# BoostConverter.net
KiCad netlist of a schematic drawn in Altium Designer
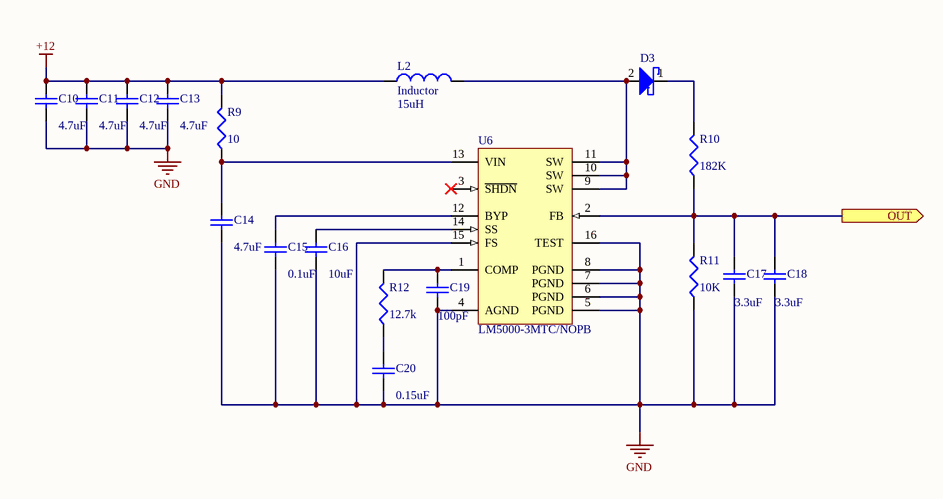
[diagram p0: BoostConverter.SchDoc]

(export (version "E")
  (design (tool "Eeschema 10.0.6"))
  (components
    (comp (ref "C10")
      (value "Cap")
      (footprint "C0805")
      (description "Capacitor")
      (fields (field (name "ALTIUM_UNNAMED_1") "4.7uF") (field (name "PUBLISHER") "Altium Limited"))
      (libsource (lib "Miscellaneous Devices") (part "Cap"))
    )
    (comp (ref "C11")
      (value "Cap")
      (footprint "C0805")
      (description "Capacitor")
      (fields (field (name "ALTIUM_UNNAMED_1") "4.7uF") (field (name "PUBLISHER") "Altium Limited"))
      (libsource (lib "Miscellaneous Devices") (part "Cap"))
    )
    (comp (ref "C12")
      (value "Cap")
      (footprint "C0805")
      (description "Capacitor")
      (fields (field (name "ALTIUM_UNNAMED_1") "4.7uF") (field (name "PUBLISHER") "Altium Limited"))
      (libsource (lib "Miscellaneous Devices") (part "Cap"))
    )
    (comp (ref "C13")
      (value "Cap")
      (footprint "C0805")
      (description "Capacitor")
      (fields (field (name "ALTIUM_UNNAMED_1") "4.7uF") (field (name "PUBLISHER") "Altium Limited"))
      (libsource (lib "Miscellaneous Devices") (part "Cap"))
    )
    (comp (ref "C14")
      (value "Cap")
      (footprint "C0805")
      (description "Capacitor")
      (fields (field (name "ALTIUM_UNNAMED_1") "4.7uF") (field (name "PUBLISHER") "Altium Limited"))
      (libsource (lib "Miscellaneous Devices") (part "Cap"))
    )
    (comp (ref "C15")
      (value "Cap")
      (footprint "C0805")
      (description "Capacitor")
      (fields (field (name "ALTIUM_UNNAMED_1") "0.1uF") (field (name "PUBLISHER") "Altium Limited"))
      (libsource (lib "Miscellaneous Devices") (part "Cap"))
    )
    (comp (ref "C16")
      (value "Cap")
      (footprint "C0805")
      (description "Capacitor")
      (fields (field (name "ALTIUM_UNNAMED_1") "10uF") (field (name "PUBLISHER") "Altium Limited"))
      (libsource (lib "Miscellaneous Devices") (part "Cap"))
    )
    (comp (ref "C17")
      (value "Cap")
      (footprint "C0805")
      (description "Capacitor")
      (fields (field (name "ALTIUM_UNNAMED_1") "3.3uF") (field (name "PUBLISHER") "Altium Limited"))
      (libsource (lib "Miscellaneous Devices") (part "Cap"))
    )
    (comp (ref "C18")
      (value "Cap")
      (footprint "C0805")
      (description "Capacitor")
      (fields (field (name "ALTIUM_UNNAMED_1") "3.3uF") (field (name "PUBLISHER") "Altium Limited"))
      (libsource (lib "Miscellaneous Devices") (part "Cap"))
    )
    (comp (ref "C19")
      (value "Cap")
      (footprint "C0805")
      (description "Capacitor")
      (fields (field (name "ALTIUM_UNNAMED_1") "100pF") (field (name "PUBLISHER") "Altium Limited"))
      (libsource (lib "Miscellaneous Devices") (part "Cap"))
    )
    (comp (ref "C20")
      (value "Cap")
      (footprint "C0805")
      (description "Capacitor")
      (fields (field (name "ALTIUM_UNNAMED_1") "0.15uF") (field (name "PUBLISHER") "Altium Limited"))
      (libsource (lib "Miscellaneous Devices") (part "Cap"))
    )
    (comp (ref "D3")
      (value "Schottky Diode")
      (footprint "DIOM4326X24N")
      (libsource (lib "IntLibrary") (part "B160-13-F"))
    )
    (comp (ref "L2")
      (value "Inductor")
      (footprint "INDC4532")
      (fields (field (name "ALTIUM_VALUE") "15uH") (field (name "PUBLISHER") "Altium Limited"))
      (libsource (lib "Miscellaneous Devices") (part "Inductor"))
    )
    (comp (ref "R9")
      (value "10")
      (footprint "J1-0603")
      (description "Resistor")
      (fields (field (name "Comment") "Res3") (field (name "PUBLISHER") "Altium Limited"))
      (libsource (lib "Miscellaneous Devices") (part "Res3"))
    )
    (comp (ref "R10")
      (value "182K")
      (footprint "J1-0603")
      (description "Resistor")
      (fields (field (name "Comment") "Res3") (field (name "PUBLISHER") "Altium Limited"))
      (libsource (lib "Miscellaneous Devices") (part "Res3"))
    )
    (comp (ref "R11")
      (value "10K")
      (footprint "J1-0603")
      (description "Resistor")
      (fields (field (name "Comment") "Res3") (field (name "PUBLISHER") "Altium Limited"))
      (libsource (lib "Miscellaneous Devices") (part "Res3"))
    )
    (comp (ref "R12")
      (value "12.7k")
      (footprint "6-0805_L")
      (description "Resistor")
      (fields (field (name "Comment") "Res3") (field (name "PUBLISHER") "Altium Limited"))
      (libsource (lib "Miscellaneous Devices") (part "Res3"))
    )
    (comp (ref "U6")
      (value "LM5000-3MTC/NOPB")
      (footprint "PW0016A_L")
      (description "High Voltage Switch Mode Regulator, 16-pin TSSOP, Pb-Free")
      (fields (field (name "MANUFACTURER") "Texas Instruments"))
      (libsource (lib "Altium Content Vault") (part "PM-SMPS-LM5000-16"))
    )
  )
  (nets
    (net (code "1") (name "+12") (class "Default")
      (node (ref "C10") (pin "2") (pinfunction "2_2") (pintype "passive"))
      (node (ref "C11") (pin "2") (pinfunction "2_2") (pintype "passive"))
      (node (ref "C12") (pin "2") (pinfunction "2_2") (pintype "passive"))
      (node (ref "C13") (pin "2") (pinfunction "2_2") (pintype "passive"))
      (node (ref "L2") (pin "1") (pinfunction "1_1") (pintype "passive"))
      (node (ref "R9") (pin "2") (pinfunction "2_2") (pintype "passive"))
    )
    (net (code "2") (name "/OUT") (class "Default")
      (node (ref "C17") (pin "2") (pinfunction "2_2") (pintype "passive"))
      (node (ref "C18") (pin "2") (pinfunction "2_2") (pintype "passive"))
      (node (ref "R10") (pin "1") (pinfunction "1_1") (pintype "passive"))
      (node (ref "R11") (pin "2") (pinfunction "2_2") (pintype "passive"))
      (node (ref "U6") (pin "2") (pinfunction "FB_2") (pintype "input"))
    )
    (net (code "3") (name "GND") (class "Default")
      (node (ref "C10") (pin "1") (pinfunction "1_1") (pintype "passive"))
      (node (ref "C11") (pin "1") (pinfunction "1_1") (pintype "passive"))
      (node (ref "C12") (pin "1") (pinfunction "1_1") (pintype "passive"))
      (node (ref "C13") (pin "1") (pinfunction "1_1") (pintype "passive"))
      (node (ref "C14") (pin "1") (pinfunction "1_1") (pintype "passive"))
      (node (ref "C15") (pin "1") (pinfunction "1_1") (pintype "passive"))
      (node (ref "C16") (pin "1") (pinfunction "1_1") (pintype "passive"))
      (node (ref "C17") (pin "1") (pinfunction "1_1") (pintype "passive"))
      (node (ref "C18") (pin "1") (pinfunction "1_1") (pintype "passive"))
      (node (ref "C19") (pin "1") (pinfunction "1_1") (pintype "passive"))
      (node (ref "C20") (pin "1") (pinfunction "1_1") (pintype "passive"))
      (node (ref "R11") (pin "1") (pinfunction "1_1") (pintype "passive"))
      (node (ref "U6") (pin "15") (pinfunction "FS_15") (pintype "input"))
      (node (ref "U6") (pin "16") (pinfunction "TEST_16") (pintype "passive"))
      (node (ref "U6") (pin "4") (pinfunction "AGND_4") (pintype "power_in"))
      (node (ref "U6") (pin "5") (pinfunction "PGND_5") (pintype "power_in"))
      (node (ref "U6") (pin "6") (pinfunction "PGND_6") (pintype "power_in"))
      (node (ref "U6") (pin "7") (pinfunction "PGND_7") (pintype "power_in"))
      (node (ref "U6") (pin "8") (pinfunction "PGND_8") (pintype "power_in"))
    )
    (net (code "4") (name "Net-(C20-Pad2)") (class "Default")
      (node (ref "C20") (pin "2") (pinfunction "2_2") (pintype "passive"))
      (node (ref "R12") (pin "1") (pinfunction "1_1") (pintype "passive"))
    )
    (net (code "5") (name "Net-(D3-Pad1)") (class "Default")
      (node (ref "D3") (pin "1") (pinfunction "1_1") (pintype "passive"))
      (node (ref "R10") (pin "2") (pinfunction "2_2") (pintype "passive"))
    )
    (net (code "6") (name "Net-(D3-Pad2)") (class "Default")
      (node (ref "D3") (pin "2") (pinfunction "2_2") (pintype "passive"))
      (node (ref "L2") (pin "2") (pinfunction "2_2") (pintype "passive"))
      (node (ref "U6") (pin "10") (pinfunction "SW_10") (pintype "power_in"))
      (node (ref "U6") (pin "11") (pinfunction "SW_11") (pintype "power_in"))
      (node (ref "U6") (pin "9") (pinfunction "SW_9") (pintype "power_in"))
    )
    (net (code "7") (name "Net-(U6-BYP)") (class "Default")
      (node (ref "C15") (pin "2") (pinfunction "2_2") (pintype "passive"))
      (node (ref "U6") (pin "12") (pinfunction "BYP_12") (pintype "passive"))
    )
    (net (code "8") (name "Net-(U6-COMP)") (class "Default")
      (node (ref "C19") (pin "2") (pinfunction "2_2") (pintype "passive"))
      (node (ref "R12") (pin "2") (pinfunction "2_2") (pintype "passive"))
      (node (ref "U6") (pin "1") (pinfunction "COMP_1") (pintype "passive"))
    )
    (net (code "9") (name "Net-(U6-SS)") (class "Default")
      (node (ref "C16") (pin "2") (pinfunction "2_2") (pintype "passive"))
      (node (ref "U6") (pin "14") (pinfunction "SS_14") (pintype "input"))
    )
    (net (code "10") (name "Net-(U6-VIN)") (class "Default")
      (node (ref "C14") (pin "2") (pinfunction "2_2") (pintype "passive"))
      (node (ref "R9") (pin "1") (pinfunction "1_1") (pintype "passive"))
      (node (ref "U6") (pin "13") (pinfunction "VIN_13") (pintype "power_in"))
    )
    (net (code "11") (name "unconnected-(U6-~{SHDN}-Pad3)") (class "Default")
      (node (ref "U6") (pin "3") (pinfunction "~{SHDN}_3") (pintype "input+no_connect"))
    )
  )
)
